# 12_-_CAN_RS232.net
KiCad netlist of a schematic drawn in Altium Designer
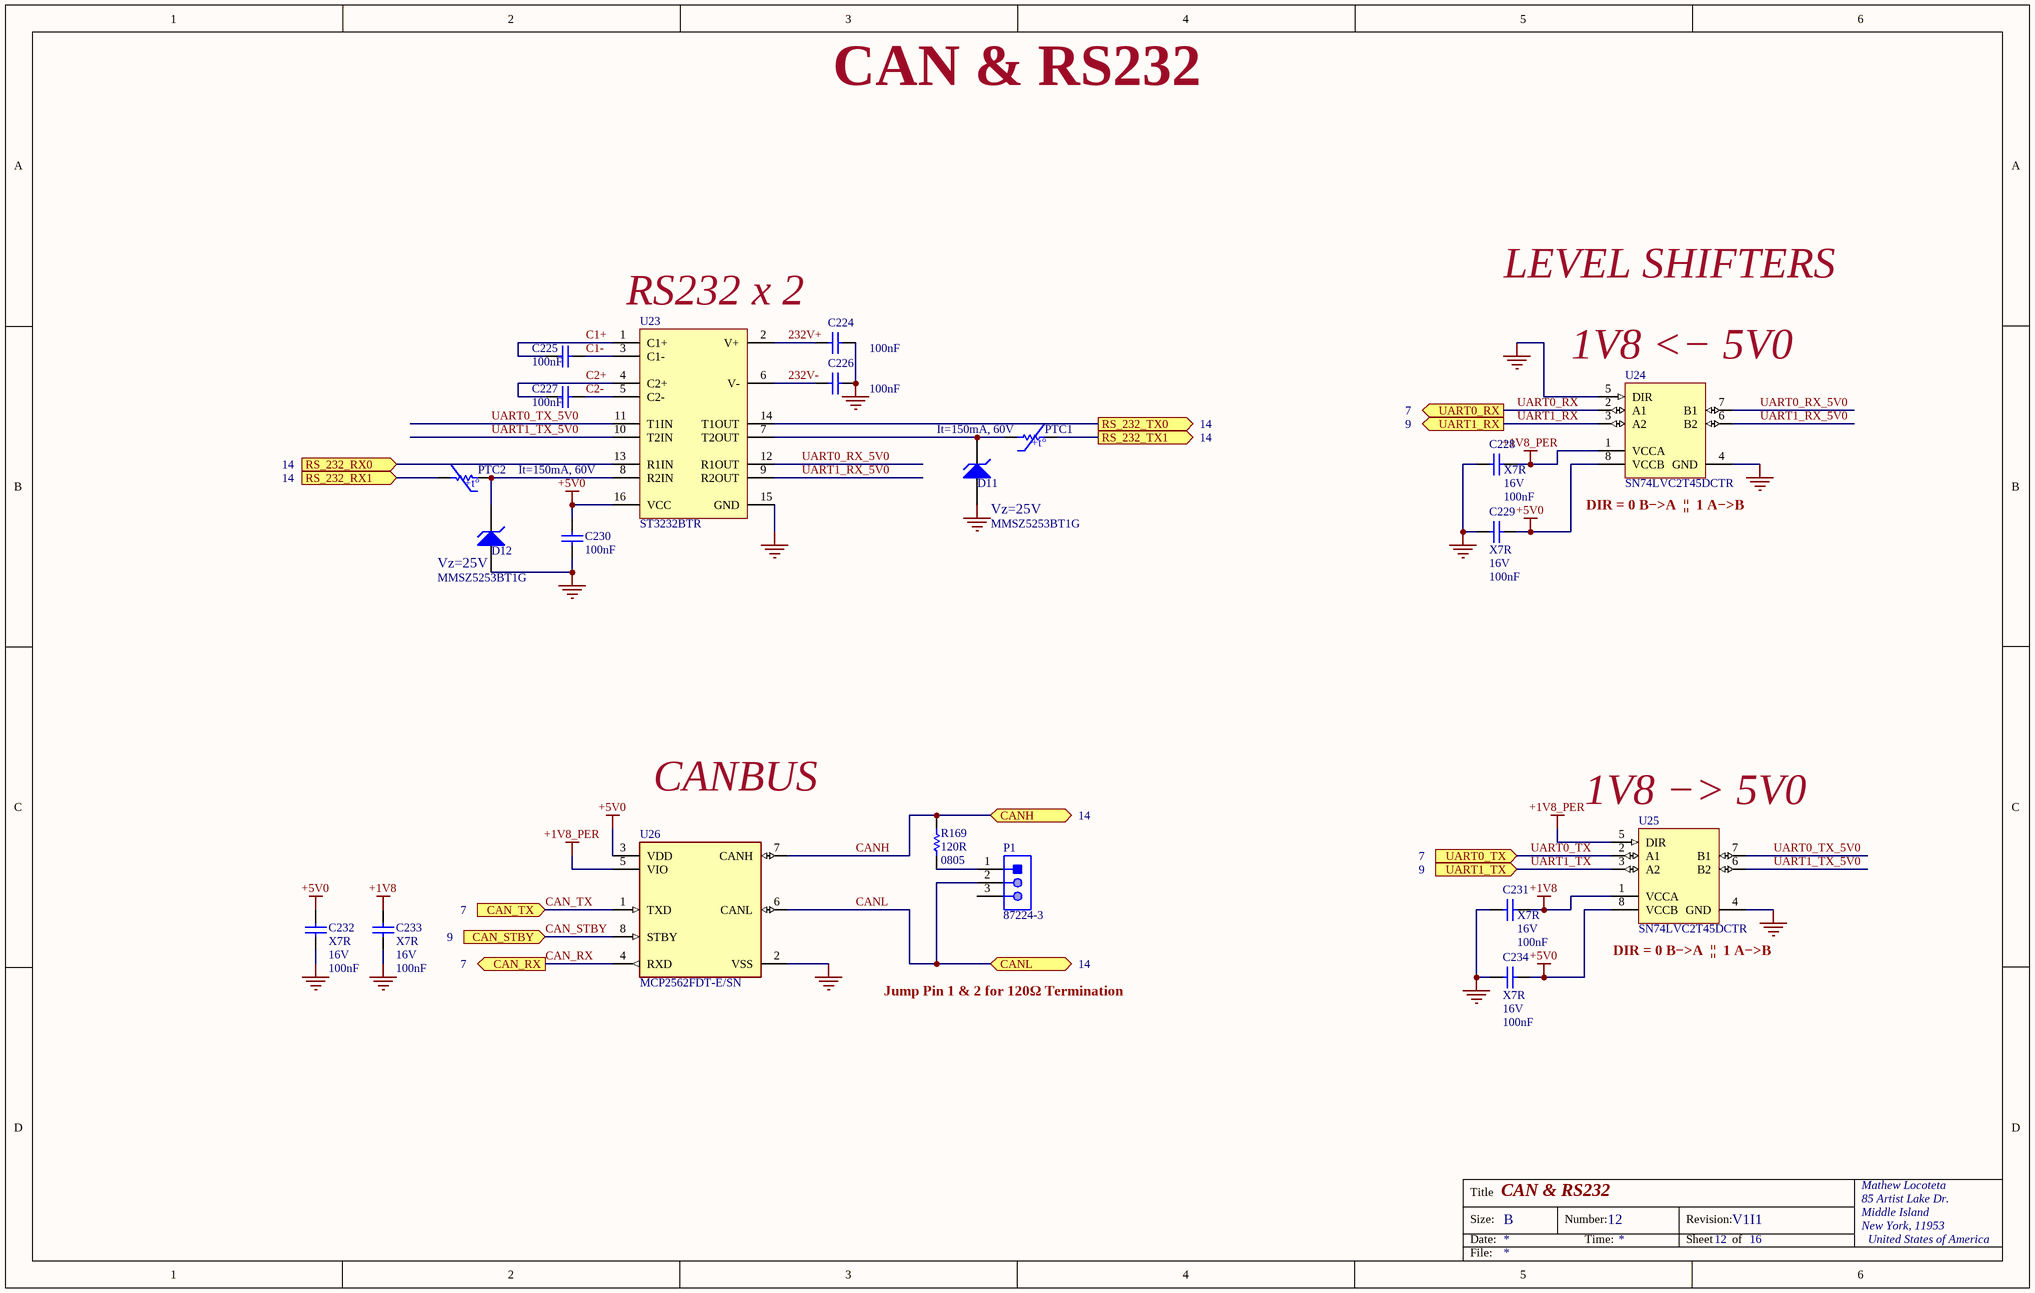
[diagram p0: [12] - CAN & RS232.SchDoc]

(export (version "E")
  (design (tool "Eeschema 10.0.6"))
  (components
    (comp (ref "C224")
      (value "100nF 0402 16V")
      (fields
        (field (name "MANUFACTURER") "KEMET")
        (field (name "MANUFACTURER PART NUMBER") "C0402C104J4RACTU")
        (field (name "TOLERANCE") "5%")
        (field (name "CAPACITANCE") "100nF")
      )
      (libsource (lib "Zynq 7000") (part "C0402C104J4RACTU"))
    )
    (comp (ref "C225")
      (value "100nF 0402 16V")
      (fields
        (field (name "MANUFACTURER") "KEMET")
        (field (name "MANUFACTURER PART NUMBER") "C0402C104J4RACTU")
        (field (name "TOLERANCE") "5%")
        (field (name "CAPACITANCE") "100nF")
      )
      (libsource (lib "Zynq 7000") (part "C0402C104J4RACTU"))
    )
    (comp (ref "C226")
      (value "100nF 0402 16V")
      (fields
        (field (name "MANUFACTURER") "KEMET")
        (field (name "MANUFACTURER PART NUMBER") "C0402C104J4RACTU")
        (field (name "TOLERANCE") "5%")
        (field (name "CAPACITANCE") "100nF")
      )
      (libsource (lib "Zynq 7000") (part "C0402C104J4RACTU"))
    )
    (comp (ref "C227")
      (value "100nF 0402 16V")
      (fields
        (field (name "MANUFACTURER") "KEMET")
        (field (name "MANUFACTURER PART NUMBER") "C0402C104J4RACTU")
        (field (name "TOLERANCE") "5%")
        (field (name "CAPACITANCE") "100nF")
      )
      (libsource (lib "Zynq 7000") (part "C0402C104J4RACTU"))
    )
    (comp (ref "C228")
      (value "100nF 0402 16V")
      (fields
        (field (name "MANUFACTURER") "KEMET")
        (field (name "MANUFACTURER PART NUMBER") "C0402C104J4RACTU")
        (field (name "TOLERANCE") "5%")
        (field (name "DIELECTRIC") "X7R")
        (field (name "VOLTAGE RATING") "16V")
        (field (name "CAPACITANCE") "100nF")
      )
      (libsource (lib "Zynq 7000") (part "C0402C104J4RACTU"))
    )
    (comp (ref "C229")
      (value "100nF 0402 16V")
      (fields
        (field (name "MANUFACTURER") "KEMET")
        (field (name "MANUFACTURER PART NUMBER") "C0402C104J4RACTU")
        (field (name "TOLERANCE") "5%")
        (field (name "DIELECTRIC") "X7R")
        (field (name "VOLTAGE RATING") "16V")
        (field (name "CAPACITANCE") "100nF")
      )
      (libsource (lib "Zynq 7000") (part "C0402C104J4RACTU"))
    )
    (comp (ref "C230")
      (value "100nF 0402 16V")
      (fields
        (field (name "MANUFACTURER") "KEMET")
        (field (name "MANUFACTURER PART NUMBER") "C0402C104J4RACTU")
        (field (name "TOLERANCE") "5%")
        (field (name "CAPACITANCE") "100nF")
      )
      (libsource (lib "Zynq 7000") (part "C0402C104J4RACTU"))
    )
    (comp (ref "C231")
      (value "100nF 0402 16V")
      (fields
        (field (name "MANUFACTURER") "KEMET")
        (field (name "MANUFACTURER PART NUMBER") "C0402C104J4RACTU")
        (field (name "TOLERANCE") "5%")
        (field (name "DIELECTRIC") "X7R")
        (field (name "VOLTAGE RATING") "16V")
        (field (name "CAPACITANCE") "100nF")
      )
      (libsource (lib "Zynq 7000") (part "C0402C104J4RACTU"))
    )
    (comp (ref "C232")
      (value "100nF 0402 16V")
      (fields
        (field (name "MANUFACTURER") "KEMET")
        (field (name "MANUFACTURER PART NUMBER") "C0402C104J4RACTU")
        (field (name "TOLERANCE") "5%")
        (field (name "DIELECTRIC") "X7R")
        (field (name "VOLTAGE RATING") "16V")
        (field (name "CAPACITANCE") "100nF")
      )
      (libsource (lib "Zynq 7000") (part "C0402C104J4RACTU"))
    )
    (comp (ref "C233")
      (value "100nF 0402 16V")
      (fields
        (field (name "MANUFACTURER") "KEMET")
        (field (name "MANUFACTURER PART NUMBER") "C0402C104J4RACTU")
        (field (name "TOLERANCE") "5%")
        (field (name "DIELECTRIC") "X7R")
        (field (name "VOLTAGE RATING") "16V")
        (field (name "CAPACITANCE") "100nF")
      )
      (libsource (lib "Zynq 7000") (part "C0402C104J4RACTU"))
    )
    (comp (ref "C234")
      (value "100nF 0402 16V")
      (fields
        (field (name "MANUFACTURER") "KEMET")
        (field (name "MANUFACTURER PART NUMBER") "C0402C104J4RACTU")
        (field (name "TOLERANCE") "5%")
        (field (name "DIELECTRIC") "X7R")
        (field (name "VOLTAGE RATING") "16V")
        (field (name "CAPACITANCE") "100nF")
      )
      (libsource (lib "Zynq 7000") (part "C0402C104J4RACTU"))
    )
    (comp (ref "D11")
      (value "MMSZ5253BT1G")
      (footprint "ONSC-SOD-123-2-425-04_V")
      (description "Zener Voltage Regulator, 500 mW, 2-Pin SOD-123, Pb-Free, Tape and Reel")
      (fields (field (name "MANUFACTURER") "On Semiconductor"))
      (libsource (lib "Altium Content Vault") (part "ONSC-K1A2-2"))
    )
    (comp (ref "D12")
      (value "MMSZ5253BT1G")
      (footprint "ONSC-SOD-123-2-425-04_V")
      (description "Zener Voltage Regulator, 500 mW, 2-Pin SOD-123, Pb-Free, Tape and Reel")
      (fields (field (name "MANUFACTURER") "On Semiconductor"))
      (libsource (lib "Altium Content Vault") (part "ONSC-K1A2-2"))
    )
    (comp (ref "P1")
      (value "87224-3")
      (footprint "TECO-87224-3_V")
      (fields (field (name "MANUFACTURER") "TE Connectivity"))
      (libsource (lib "Altium Content Vault") (part "CN-1P-M-R3"))
    )
    (comp (ref "PTC1")
      (value "It=150mA, 60V")
      (footprint "R1206")
      (description "PTC RESET FUSE 60V 50MA 1206")
      (fields (field (name "MANUFACTURER") "Bel") (field (name "MANUFACTURER PART NUMBER") "0ZCJ0005FF2E"))
      (libsource (lib "DVXC4+ ECU (2)") (part "0ZCJ0005FF2E"))
    )
    (comp (ref "PTC2")
      (value "It=150mA, 60V")
      (footprint "R1206")
      (description "PTC RESET FUSE 60V 50MA 1206")
      (fields (field (name "MANUFACTURER") "Bel") (field (name "MANUFACTURER PART NUMBER") "0ZCJ0005FF2E"))
      (libsource (lib "DVXC4+ ECU (2)") (part "0ZCJ0005FF2E"))
    )
    (comp (ref "R169")
      (value "120R")
      (footprint "RESC2013X50X30LL20T20")
      (fields
        (field (name "PART NUMBER") "CRCW0805120RJNEA")
        (field (name "MANUFACTURER") "Vishay Dale")
        (field (name "CASE") "0805")
      )
      (libsource (lib "Altium Content Vault") (part "RES"))
    )
    (comp (ref "U23")
      (value "ST3232BTR")
      (footprint "STM-TSSOP-16_L")
      (description "RS-232 Driver and Receiver, 3 to 5.5 V, -40 to 85 degC, 16-Pin TSSOP, RoHS, Tape and Reel")
      (fields (field (name "MANUFACTURER") "STMicroelectronics"))
      (libsource (lib "Altium Content Vault") (part "STM-ST3232-TSSOP-16"))
    )
    (comp (ref "U24")
      (value "SN74LVC2T45DCTR")
      (footprint "DCT0008A_N")
      (fields
        (field (name "MANUFACTURER") "Texas Instruments")
        (field (name "GENERIC PART NUMBER") "SN74LVC2T45")
      )
      (libsource (lib "Altium Content Vault") (part "TI-SN74XVC2T45-8"))
    )
    (comp (ref "U25")
      (value "SN74LVC2T45DCTR")
      (footprint "DCT0008A_N")
      (fields
        (field (name "MANUFACTURER") "Texas Instruments")
        (field (name "GENERIC PART NUMBER") "SN74LVC2T45")
      )
      (libsource (lib "Altium Content Vault") (part "TI-SN74XVC2T45-8"))
    )
    (comp (ref "U26")
      (value "MCP2562FDT-E/SN")
      (footprint "FP-C04-057-SN-MFG")
      (description "IC TRANSCEIVER 1/1 8SOIC")
      (libsource (lib "Altium Content Vault") (part "fcb6c66e4429206983adab9201371df"))
    )
  )
  (nets
    (net (code "1") (name "+1V8") (class "Default")
      (node (ref "C231") (pin "1") (pinfunction "1_1") (pintype "passive"))
      (node (ref "C233") (pin "2") (pinfunction "2_2") (pintype "passive"))
      (node (ref "U25") (pin "1") (pinfunction "VCCA_1") (pintype "power_in"))
    )
    (net (code "2") (name "+1V8_PER") (class "Default")
      (node (ref "C228") (pin "1") (pinfunction "1_1") (pintype "passive"))
      (node (ref "U24") (pin "1") (pinfunction "VCCA_1") (pintype "power_in"))
      (node (ref "U25") (pin "5") (pinfunction "DIR_5") (pintype "input"))
      (node (ref "U26") (pin "5") (pinfunction "VIO_5") (pintype "power_in"))
    )
    (net (code "3") (name "+5V0") (class "Default")
      (node (ref "C229") (pin "2") (pinfunction "2_2") (pintype "passive"))
      (node (ref "C230") (pin "2") (pinfunction "2_2") (pintype "passive"))
      (node (ref "C232") (pin "2") (pinfunction "2_2") (pintype "passive"))
      (node (ref "C234") (pin "2") (pinfunction "2_2") (pintype "passive"))
      (node (ref "U23") (pin "16") (pinfunction "VCC_16") (pintype "passive"))
      (node (ref "U24") (pin "8") (pinfunction "VCCB_8") (pintype "power_in"))
      (node (ref "U25") (pin "8") (pinfunction "VCCB_8") (pintype "power_in"))
      (node (ref "U26") (pin "3") (pinfunction "VDD_3") (pintype "power_in"))
    )
    (net (code "4") (name "/232V+") (class "Default")
      (node (ref "C224") (pin "2") (pinfunction "2_2") (pintype "passive"))
      (node (ref "U23") (pin "2") (pinfunction "V+_2") (pintype "passive"))
    )
    (net (code "5") (name "/232V-") (class "Default")
      (node (ref "C226") (pin "2") (pinfunction "2_2") (pintype "passive"))
      (node (ref "U23") (pin "6") (pinfunction "V-_6") (pintype "passive"))
    )
    (net (code "6") (name "/C1+") (class "Default")
      (node (ref "C225") (pin "1") (pinfunction "1_1") (pintype "passive"))
      (node (ref "U23") (pin "1") (pinfunction "C1+_1") (pintype "passive"))
    )
    (net (code "7") (name "/C1-") (class "Default")
      (node (ref "C225") (pin "2") (pinfunction "2_2") (pintype "passive"))
      (node (ref "U23") (pin "3") (pinfunction "C1-_3") (pintype "passive"))
    )
    (net (code "8") (name "/C2+") (class "Default")
      (node (ref "C227") (pin "1") (pinfunction "1_1") (pintype "passive"))
      (node (ref "U23") (pin "4") (pinfunction "C2+_4") (pintype "passive"))
    )
    (net (code "9") (name "/C2-") (class "Default")
      (node (ref "C227") (pin "2") (pinfunction "2_2") (pintype "passive"))
      (node (ref "U23") (pin "5") (pinfunction "C2-_5") (pintype "passive"))
    )
    (net (code "10") (name "/CANH") (class "Default")
      (node (ref "R169") (pin "1") (pinfunction "1_1") (pintype "passive"))
      (node (ref "U26") (pin "7") (pinfunction "CANH_7") (pintype "bidirectional"))
    )
    (net (code "11") (name "/CANL") (class "Default")
      (node (ref "P1") (pin "2") (pinfunction "2_2") (pintype "passive"))
      (node (ref "U26") (pin "6") (pinfunction "CANL_6") (pintype "bidirectional"))
    )
    (net (code "12") (name "/CAN_RX") (class "Default")
      (node (ref "U26") (pin "4") (pinfunction "RXD_4") (pintype "output"))
    )
    (net (code "13") (name "/CAN_STBY") (class "Default")
      (node (ref "U26") (pin "8") (pinfunction "STBY_8") (pintype "input"))
    )
    (net (code "14") (name "/CAN_TX") (class "Default")
      (node (ref "U26") (pin "1") (pinfunction "TXD_1") (pintype "input"))
    )
    (net (code "15") (name "/RS_232_RX0") (class "Default")
      (node (ref "U23") (pin "13") (pinfunction "R1IN_13") (pintype "passive"))
    )
    (net (code "16") (name "/RS_232_RX1") (class "Default")
      (node (ref "PTC2") (pin "2") (pinfunction "2_2") (pintype "passive"))
    )
    (net (code "17") (name "/RS_232_TX0") (class "Default")
      (node (ref "U23") (pin "14") (pinfunction "T1OUT_14") (pintype "passive"))
    )
    (net (code "18") (name "/RS_232_TX1") (class "Default")
      (node (ref "PTC1") (pin "2") (pinfunction "2_2") (pintype "passive"))
    )
    (net (code "19") (name "/UART0_RX") (class "Default")
      (node (ref "U24") (pin "2") (pinfunction "A1_2") (pintype "bidirectional"))
    )
    (net (code "20") (name "/UART0_RX_5V0") (class "Default")
      (node (ref "U23") (pin "12") (pinfunction "R1OUT_12") (pintype "passive"))
      (node (ref "U24") (pin "7") (pinfunction "B1_7") (pintype "bidirectional"))
    )
    (net (code "21") (name "/UART0_TX") (class "Default")
      (node (ref "U25") (pin "2") (pinfunction "A1_2") (pintype "bidirectional"))
    )
    (net (code "22") (name "/UART0_TX_5V0") (class "Default")
      (node (ref "U23") (pin "11") (pinfunction "T1IN_11") (pintype "passive"))
      (node (ref "U25") (pin "7") (pinfunction "B1_7") (pintype "bidirectional"))
    )
    (net (code "23") (name "/UART1_RX") (class "Default")
      (node (ref "U24") (pin "3") (pinfunction "A2_3") (pintype "bidirectional"))
    )
    (net (code "24") (name "/UART1_RX_5V0") (class "Default")
      (node (ref "U23") (pin "9") (pinfunction "R2OUT_9") (pintype "passive"))
      (node (ref "U24") (pin "6") (pinfunction "B2_6") (pintype "bidirectional"))
    )
    (net (code "25") (name "/UART1_TX") (class "Default")
      (node (ref "U25") (pin "3") (pinfunction "A2_3") (pintype "bidirectional"))
    )
    (net (code "26") (name "/UART1_TX_5V0") (class "Default")
      (node (ref "U23") (pin "10") (pinfunction "T2IN_10") (pintype "passive"))
      (node (ref "U25") (pin "6") (pinfunction "B2_6") (pintype "bidirectional"))
    )
    (net (code "27") (name "GND") (class "Default")
      (node (ref "C224") (pin "1") (pinfunction "1_1") (pintype "passive"))
      (node (ref "C226") (pin "1") (pinfunction "1_1") (pintype "passive"))
      (node (ref "C228") (pin "2") (pinfunction "2_2") (pintype "passive"))
      (node (ref "C229") (pin "1") (pinfunction "1_1") (pintype "passive"))
      (node (ref "C230") (pin "1") (pinfunction "1_1") (pintype "passive"))
      (node (ref "C231") (pin "2") (pinfunction "2_2") (pintype "passive"))
      (node (ref "C232") (pin "1") (pinfunction "1_1") (pintype "passive"))
      (node (ref "C233") (pin "1") (pinfunction "1_1") (pintype "passive"))
      (node (ref "C234") (pin "1") (pinfunction "1_1") (pintype "passive"))
      (node (ref "D11") (pin "2") (pinfunction "A_2") (pintype "passive"))
      (node (ref "D12") (pin "2") (pinfunction "A_2") (pintype "passive"))
      (node (ref "U23") (pin "15") (pinfunction "GND_15") (pintype "passive"))
      (node (ref "U24") (pin "4") (pinfunction "GND_4") (pintype "power_in"))
      (node (ref "U24") (pin "5") (pinfunction "DIR_5") (pintype "input"))
      (node (ref "U25") (pin "4") (pinfunction "GND_4") (pintype "power_in"))
      (node (ref "U26") (pin "2") (pinfunction "VSS_2") (pintype "power_in"))
    )
    (net (code "28") (name "Net-(D11-K)") (class "Default")
      (node (ref "D11") (pin "1") (pinfunction "K_1") (pintype "passive"))
      (node (ref "PTC1") (pin "1") (pinfunction "1_1") (pintype "passive"))
      (node (ref "U23") (pin "7") (pinfunction "T2OUT_7") (pintype "passive"))
    )
    (net (code "29") (name "Net-(D12-K)") (class "Default")
      (node (ref "D12") (pin "1") (pinfunction "K_1") (pintype "passive"))
      (node (ref "PTC2") (pin "1") (pinfunction "1_1") (pintype "passive"))
      (node (ref "U23") (pin "8") (pinfunction "R2IN_8") (pintype "passive"))
    )
    (net (code "30") (name "Net-(P1-Pad1)") (class "Default")
      (node (ref "P1") (pin "1") (pinfunction "1_1") (pintype "passive"))
      (node (ref "R169") (pin "2") (pinfunction "2_2") (pintype "passive"))
    )
    (net (code "31") (name "unconnected-(P1-Pad3)") (class "Default")
      (node (ref "P1") (pin "3") (pinfunction "3_3") (pintype "passive"))
    )
  )
)
